# tweeq-BattCharger_v1.net
KiCad netlist of a schematic drawn in EAGLE
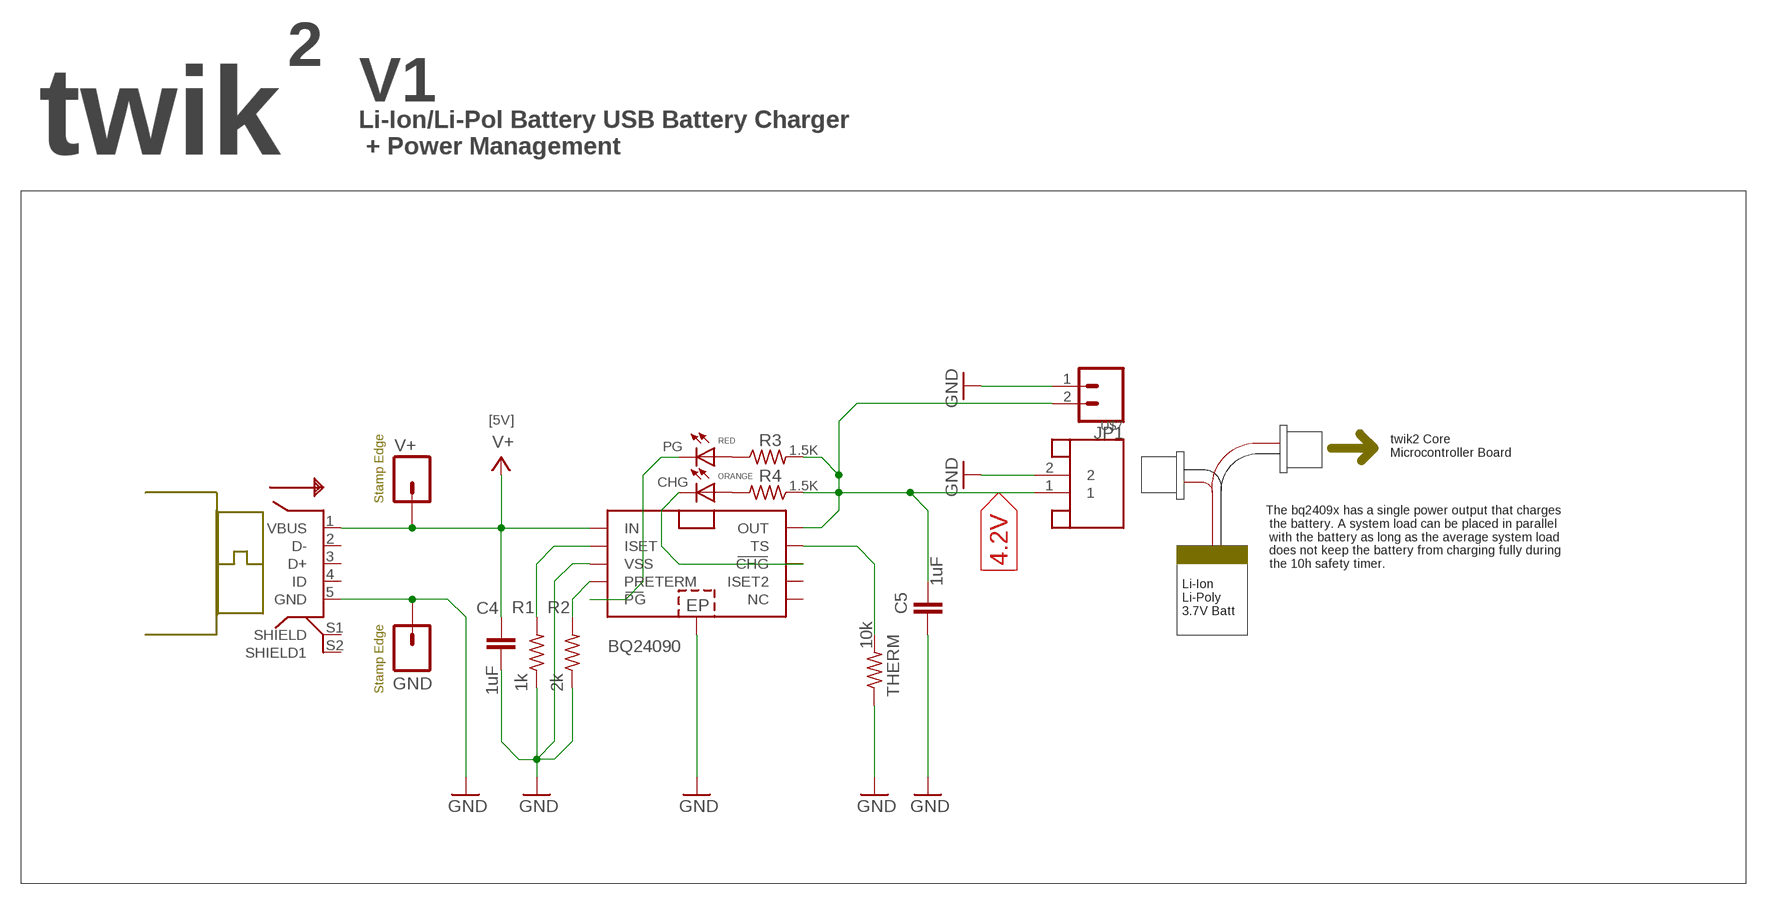
[diagram p0: schematic, sheet 1]

(export (version "E")
  (design (tool "Eeschema 10.0.6"))
  (components
    (comp (ref "BQ24090")
      (value "BQ2409X-DGQ")
      (footprint "eagle-import:MSOP10_POWERPAD")
      (libsource (lib "eagle-import") (part "BQ2409X-DGQ"))
    )
    (comp (ref "C4")
      (value "1uF")
      (footprint "eagle-import:C0603K")
      (libsource (lib "eagle-import") (part "C-EUC0603K"))
    )
    (comp (ref "C5")
      (value "1uF")
      (footprint "eagle-import:C0603K")
      (libsource (lib "eagle-import") (part "C-EUC0603K"))
    )
    (comp (ref "CHG")
      (value "ORANGE")
      (footprint "eagle-import:CHIP-LED0603")
      (libsource (lib "eagle-import") (part "LEDCHIP-LED0603"))
    )
    (comp (ref "GND")
      (value "M01SQ_NS")
      (footprint "eagle-import:1X01_SQ")
      (libsource (lib "eagle-import") (part "M01SQ_NS"))
    )
    (comp (ref "JP1")
      (value "M022.54-POL-TH")
      (footprint "eagle-import:1X02_2.54POL_TH")
      (libsource (lib "eagle-import") (part "M022.54-POL-TH"))
    )
    (comp (ref "PG")
      (value "RED")
      (footprint "eagle-import:CHIP-LED0603")
      (libsource (lib "eagle-import") (part "LEDCHIP-LED0603"))
    )
    (comp (ref "R1")
      (value "1k")
      (footprint "eagle-import:R0402")
      (libsource (lib "eagle-import") (part "R-US_R0402"))
    )
    (comp (ref "R2")
      (value "2k")
      (footprint "eagle-import:R0402")
      (libsource (lib "eagle-import") (part "R-US_R0402"))
    )
    (comp (ref "R3")
      (value "1.5K")
      (footprint "eagle-import:R0402")
      (libsource (lib "eagle-import") (part "R-US_R0402"))
    )
    (comp (ref "R4")
      (value "1.5K")
      (footprint "eagle-import:R0402")
      (libsource (lib "eagle-import") (part "R-US_R0402"))
    )
    (comp (ref "THERM")
      (value "10k")
      (footprint "eagle-import:R0402")
      (libsource (lib "eagle-import") (part "R-US_R0402"))
    )
    (comp (ref "U$2")
      (value "USB/MICRO-5PF-B")
      (footprint "eagle-import:MICRO_USB_5PF_B")
      (libsource (lib "eagle-import") (part "USB/MICRO-5PF-B"))
    )
    (comp (ref "U$7")
      (value "JST-2PINSH")
      (footprint "eagle-import:SH1.0-2PIN")
      (libsource (lib "eagle-import") (part "JST-2PINSH"))
    )
    (comp (ref "V+")
      (value "M01/R_NS")
      (footprint "eagle-import:1X01NS")
      (libsource (lib "eagle-import") (part "M01/R_NS"))
    )
  )
  (nets
    (net (code "1") (name "4.2V") (class "Default")
      (node (ref "BQ24090") (pin "10") (pinfunction "OUT_10") (pintype "bidirectional"))
      (node (ref "C5") (pin "2") (pinfunction "2_2") (pintype "passive"))
      (node (ref "JP1") (pin "2") (pinfunction "2_2") (pintype "passive"))
      (node (ref "R3") (pin "2") (pinfunction "2_2") (pintype "passive"))
      (node (ref "R4") (pin "1") (pinfunction "1_1") (pintype "passive"))
      (node (ref "U$7") (pin "1") (pinfunction "1_1") (pintype "bidirectional"))
    )
    (net (code "2") (name "GND") (class "Default")
      (node (ref "BQ24090") (pin "3") (pinfunction "VSS_3") (pintype "bidirectional"))
      (node (ref "BQ24090") (pin "EP") (pinfunction "EP_EP") (pintype "bidirectional"))
      (node (ref "C4") (pin "2") (pinfunction "2_2") (pintype "passive"))
      (node (ref "C5") (pin "1") (pinfunction "1_1") (pintype "passive"))
      (node (ref "GND") (pin "1") (pinfunction "1_1") (pintype "passive"))
      (node (ref "JP1") (pin "1") (pinfunction "1_1") (pintype "passive"))
      (node (ref "R1") (pin "1") (pinfunction "1_1") (pintype "passive"))
      (node (ref "R2") (pin "1") (pinfunction "1_1") (pintype "passive"))
      (node (ref "THERM") (pin "1") (pinfunction "1_1") (pintype "passive"))
      (node (ref "U$2") (pin "5") (pinfunction "GND_5") (pintype "bidirectional"))
      (node (ref "U$7") (pin "2") (pinfunction "2_2") (pintype "bidirectional"))
    )
    (net (code "3") (name "Net-(BQ24090-CHG)") (class "Default")
      (node (ref "BQ24090") (pin "8") (pinfunction "CHG_8") (pintype "bidirectional"))
      (node (ref "CHG") (pin "C") (pinfunction "C_C") (pintype "passive"))
    )
    (net (code "4") (name "Net-(BQ24090-ISET)") (class "Default")
      (node (ref "BQ24090") (pin "2") (pinfunction "ISET_2") (pintype "bidirectional"))
      (node (ref "R1") (pin "2") (pinfunction "2_2") (pintype "passive"))
    )
    (net (code "5") (name "Net-(BQ24090-PG)") (class "Default")
      (node (ref "BQ24090") (pin "5") (pinfunction "PG_5") (pintype "bidirectional"))
      (node (ref "PG") (pin "C") (pinfunction "C_C") (pintype "passive"))
    )
    (net (code "6") (name "Net-(BQ24090-PRETERM)") (class "Default")
      (node (ref "BQ24090") (pin "4") (pinfunction "PRETERM_4") (pintype "bidirectional"))
      (node (ref "R2") (pin "2") (pinfunction "2_2") (pintype "passive"))
    )
    (net (code "7") (name "Net-(BQ24090-TS)") (class "Default")
      (node (ref "BQ24090") (pin "9") (pinfunction "TS_9") (pintype "bidirectional"))
      (node (ref "THERM") (pin "2") (pinfunction "2_2") (pintype "passive"))
    )
    (net (code "8") (name "Net-(CHG-PadA)") (class "Default")
      (node (ref "CHG") (pin "A") (pinfunction "A_A") (pintype "passive"))
      (node (ref "R4") (pin "2") (pinfunction "2_2") (pintype "passive"))
    )
    (net (code "9") (name "Net-(PG-PadA)") (class "Default")
      (node (ref "PG") (pin "A") (pinfunction "A_A") (pintype "passive"))
      (node (ref "R3") (pin "1") (pinfunction "1_1") (pintype "passive"))
    )
    (net (code "10") (name "V+") (class "Default")
      (node (ref "BQ24090") (pin "1") (pinfunction "IN_1") (pintype "bidirectional"))
      (node (ref "C4") (pin "1") (pinfunction "1_1") (pintype "passive"))
      (node (ref "U$2") (pin "1") (pinfunction "VBUS_1") (pintype "bidirectional"))
      (node (ref "V+") (pin "1") (pinfunction "1_1") (pintype "passive"))
    )
    (net (code "11") (name "unconnected-(BQ24090-ISET2-Pad7)") (class "Default")
      (node (ref "BQ24090") (pin "7") (pinfunction "ISET2_7") (pintype "bidirectional"))
    )
    (net (code "12") (name "unconnected-(BQ24090-NC-Pad6)") (class "Default")
      (node (ref "BQ24090") (pin "6") (pinfunction "NC_6") (pintype "bidirectional"))
    )
    (net (code "13") (name "unconnected-(U$2-D+-Pad3)") (class "Default")
      (node (ref "U$2") (pin "3") (pinfunction "D+_3") (pintype "bidirectional"))
    )
    (net (code "14") (name "unconnected-(U$2-D--Pad2)") (class "Default")
      (node (ref "U$2") (pin "2") (pinfunction "D-_2") (pintype "bidirectional"))
    )
    (net (code "15") (name "unconnected-(U$2-ID-Pad4)") (class "Default")
      (node (ref "U$2") (pin "4") (pinfunction "ID_4") (pintype "bidirectional"))
    )
    (net (code "16") (name "unconnected-(U$2-SHIELD-PadS1)") (class "Default")
      (node (ref "U$2") (pin "S1") (pinfunction "SHIELD_S1") (pintype "bidirectional"))
    )
    (net (code "17") (name "unconnected-(U$2-SHIELD1-PadS2)") (class "Default")
      (node (ref "U$2") (pin "S2") (pinfunction "SHIELD1_S2") (pintype "bidirectional"))
    )
  )
)
